# TFT-Display.net
KiCad netlist of a schematic drawn in EAGLE
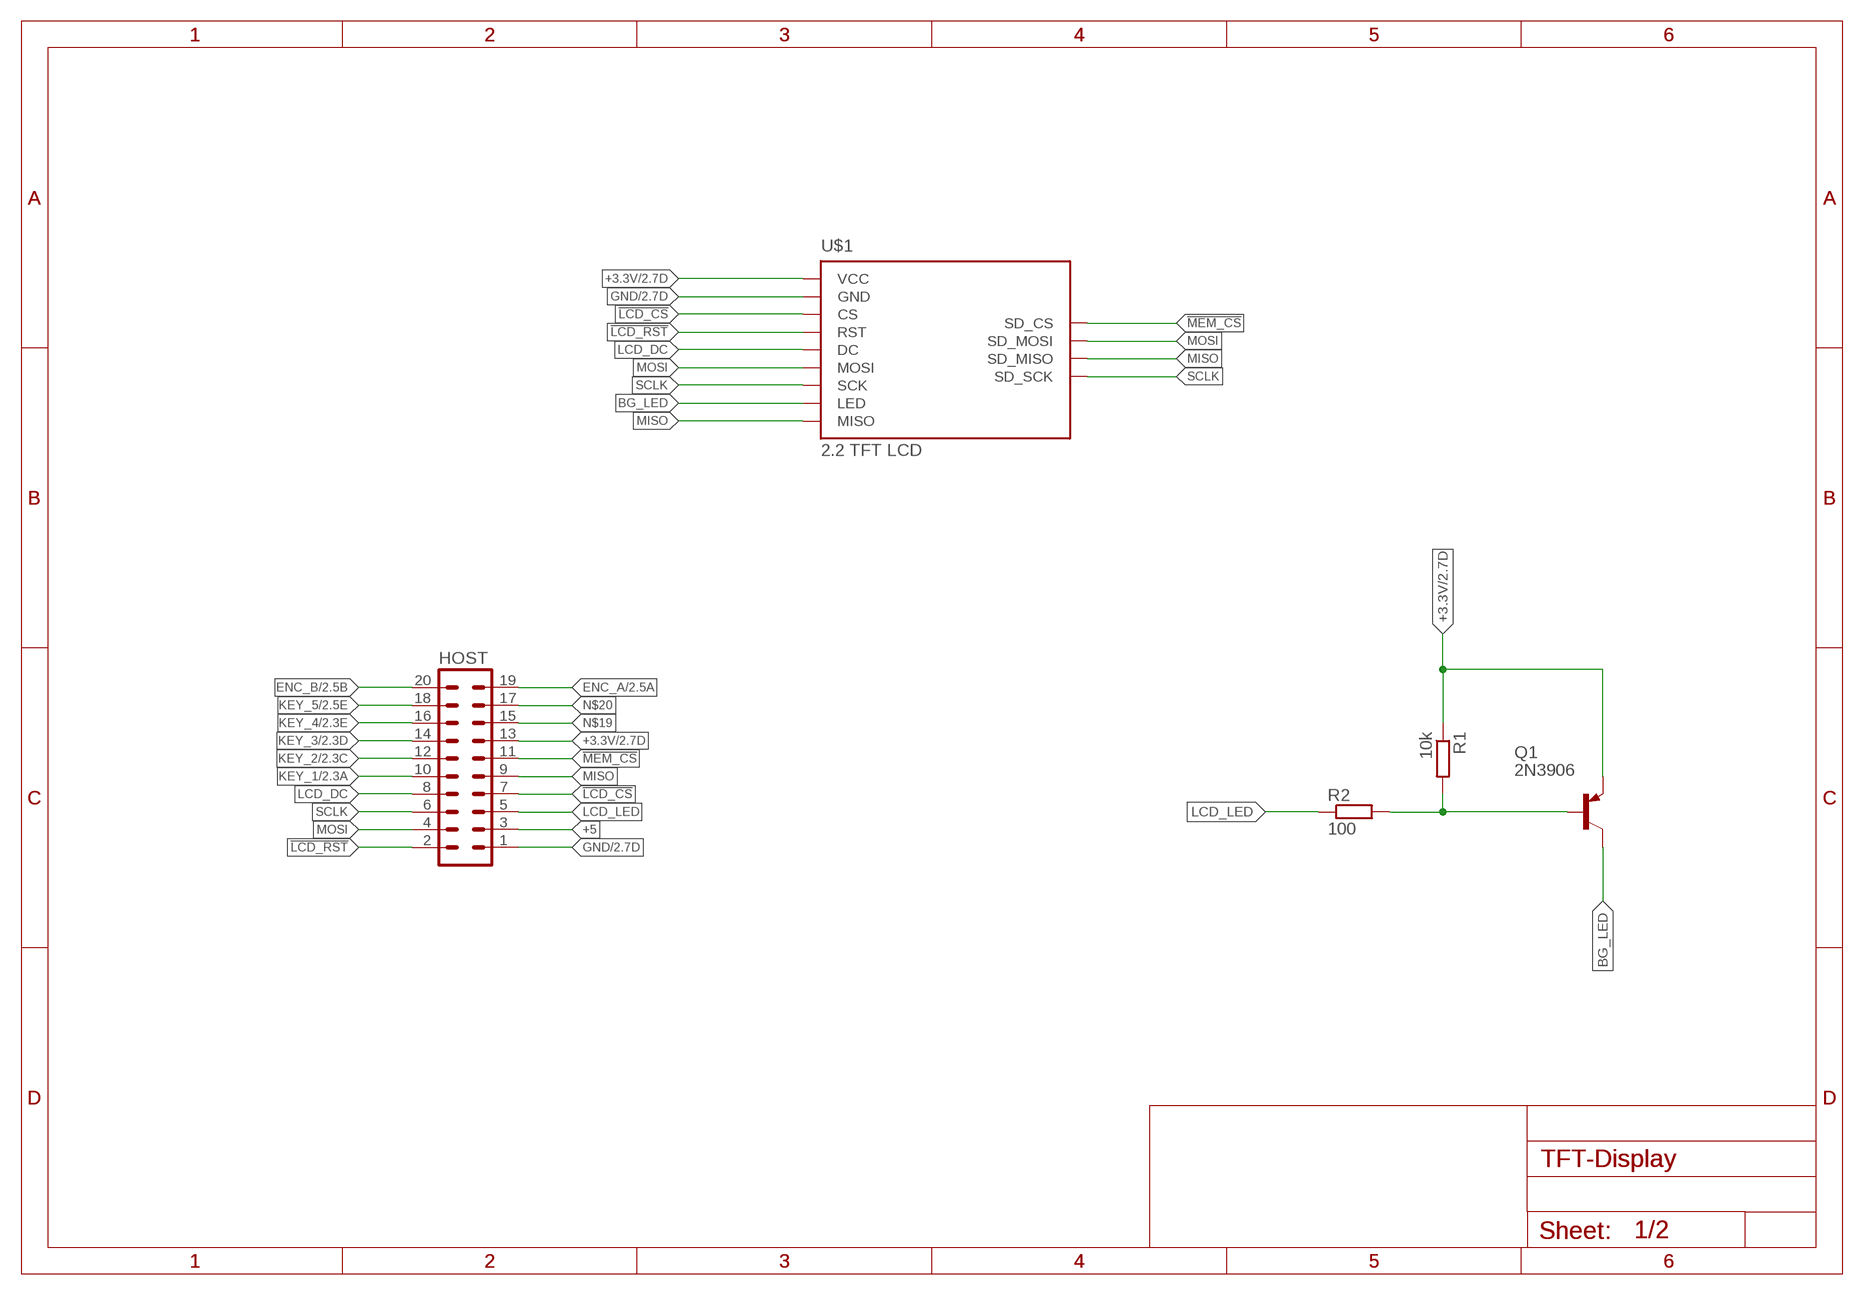
[diagram p0: schematic, sheet 1]
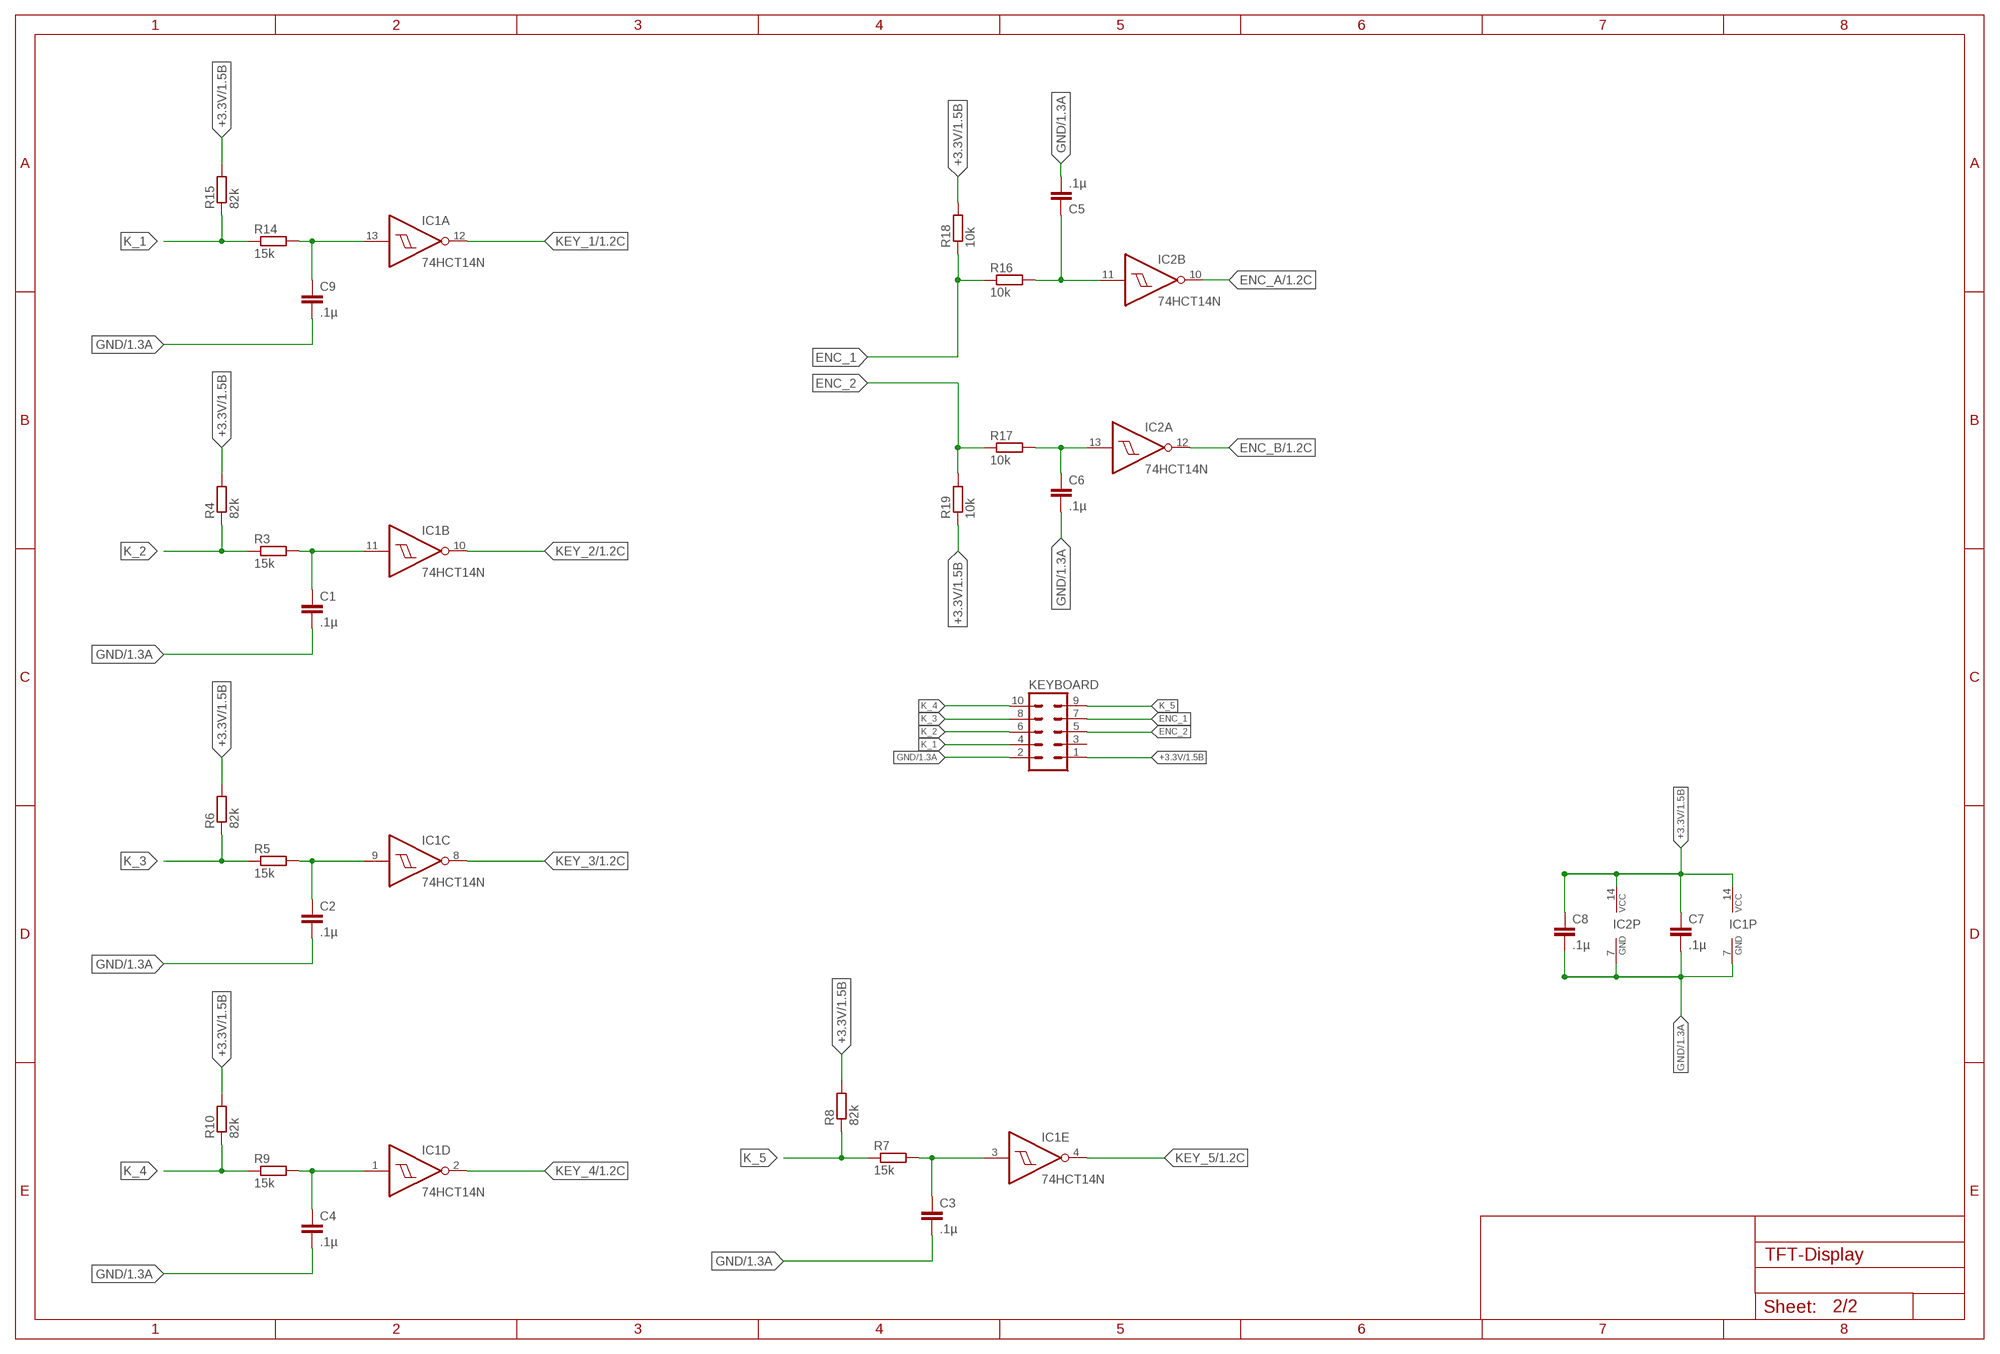
[diagram p1: schematic, sheet 2]

(export (version "E")
  (design (tool "Eeschema 10.0.6"))
  (components
    (comp (ref "C1")
      (value ".1µ")
      (footprint "eagle-import:C025-024X044")
      (libsource (lib "eagle-import") (part "C-EU025-024X044"))
    )
    (comp (ref "C2")
      (value ".1µ")
      (footprint "eagle-import:C025-024X044")
      (libsource (lib "eagle-import") (part "C-EU025-024X044"))
    )
    (comp (ref "C3")
      (value ".1µ")
      (footprint "eagle-import:C025-024X044")
      (libsource (lib "eagle-import") (part "C-EU025-024X044"))
    )
    (comp (ref "C4")
      (value ".1µ")
      (footprint "eagle-import:C025-024X044")
      (libsource (lib "eagle-import") (part "C-EU025-024X044"))
    )
    (comp (ref "C5")
      (value ".1µ")
      (footprint "eagle-import:C025-024X044")
      (libsource (lib "eagle-import") (part "C-EU025-024X044"))
    )
    (comp (ref "C6")
      (value ".1µ")
      (footprint "eagle-import:C025-024X044")
      (libsource (lib "eagle-import") (part "C-EU025-024X044"))
    )
    (comp (ref "C7")
      (value ".1µ")
      (footprint "eagle-import:C025-024X044")
      (libsource (lib "eagle-import") (part "C-EU025-024X044"))
    )
    (comp (ref "C8")
      (value ".1µ")
      (footprint "eagle-import:C025-024X044")
      (libsource (lib "eagle-import") (part "C-EU025-024X044"))
    )
    (comp (ref "C9")
      (value ".1µ")
      (footprint "eagle-import:C025-024X044")
      (libsource (lib "eagle-import") (part "C-EU025-024X044"))
    )
    (comp (ref "IC1")
      (value "74HCT14N")
      (footprint "eagle-import:DIL14")
      (libsource (lib "eagle-import") (part "7414NHCT"))
    )
    (comp (ref "IC2")
      (value "74HCT14N")
      (footprint "eagle-import:DIL14")
      (libsource (lib "eagle-import") (part "7414NHCT"))
    )
    (comp (ref "KEYBOARD")
      (value "ML10L")
      (footprint "eagle-import:ML10L")
      (libsource (lib "eagle-import") (part "ML10L"))
    )
    (comp (ref "R3")
      (value "15k")
      (footprint "eagle-import:0204_7")
      (libsource (lib "eagle-import") (part "R-EU_0204/7"))
    )
    (comp (ref "R4")
      (value "82k")
      (footprint "eagle-import:0204_7")
      (libsource (lib "eagle-import") (part "R-EU_0204/7"))
    )
    (comp (ref "R5")
      (value "15k")
      (footprint "eagle-import:0204_7")
      (libsource (lib "eagle-import") (part "R-EU_0204/7"))
    )
    (comp (ref "R6")
      (value "82k")
      (footprint "eagle-import:0204_7")
      (libsource (lib "eagle-import") (part "R-EU_0204/7"))
    )
    (comp (ref "R7")
      (value "15k")
      (footprint "eagle-import:0204_7")
      (libsource (lib "eagle-import") (part "R-EU_0204/7"))
    )
    (comp (ref "R8")
      (value "82k")
      (footprint "eagle-import:0204_7")
      (libsource (lib "eagle-import") (part "R-EU_0204/7"))
    )
    (comp (ref "R9")
      (value "15k")
      (footprint "eagle-import:0204_7")
      (libsource (lib "eagle-import") (part "R-EU_0204/7"))
    )
    (comp (ref "R10")
      (value "82k")
      (footprint "eagle-import:0204_7")
      (libsource (lib "eagle-import") (part "R-EU_0204/7"))
    )
    (comp (ref "R14")
      (value "15k")
      (footprint "eagle-import:0204_7")
      (libsource (lib "eagle-import") (part "R-EU_0204/7"))
    )
    (comp (ref "R15")
      (value "82k")
      (footprint "eagle-import:0204_7")
      (libsource (lib "eagle-import") (part "R-EU_0204/7"))
    )
    (comp (ref "R16")
      (value "10k")
      (footprint "eagle-import:0204_7")
      (libsource (lib "eagle-import") (part "R-EU_0204/7"))
    )
    (comp (ref "R17")
      (value "10k")
      (footprint "eagle-import:0204_7")
      (libsource (lib "eagle-import") (part "R-EU_0204/7"))
    )
    (comp (ref "R18")
      (value "10k")
      (footprint "eagle-import:0204_7")
      (libsource (lib "eagle-import") (part "R-EU_0204/7"))
    )
    (comp (ref "R19")
      (value "10k")
      (footprint "eagle-import:0204_7")
      (libsource (lib "eagle-import") (part "R-EU_0204/7"))
    )
    (comp (ref "HOST")
      (value "ML20L")
      (footprint "eagle-import:ML20L")
      (libsource (lib "eagle-import") (part "ML20L"))
    )
    (comp (ref "Q1")
      (value "2N3906")
      (footprint "eagle-import:TO92")
      (libsource (lib "eagle-import") (part "2N3906"))
    )
    (comp (ref "R1")
      (value "10k")
      (footprint "eagle-import:0204_7")
      (libsource (lib "eagle-import") (part "R-EU_0204/7"))
    )
    (comp (ref "R2")
      (value "100")
      (footprint "eagle-import:0204_7")
      (libsource (lib "eagle-import") (part "R-EU_0204/7"))
    )
    (comp (ref "U$1")
      (value "2.2_TFT_LCDNEW")
      (footprint "eagle-import:2.2_TFT_LCD_LEDSEE")
      (libsource (lib "eagle-import") (part "2.2_TFT_LCDNEW"))
    )
  )
  (nets
    (net (code "1") (name "+3.3V") (class "Default")
      (node (ref "C7") (pin "1") (pinfunction "1_1") (pintype "passive"))
      (node (ref "C8") (pin "1") (pinfunction "1_1") (pintype "passive"))
      (node (ref "HOST") (pin "13") (pinfunction "13_13") (pintype "passive"))
      (node (ref "IC1") (pin "14") (pinfunction "VCC_14") (pintype "power_in"))
      (node (ref "IC2") (pin "14") (pinfunction "VCC_14") (pintype "power_in"))
      (node (ref "KEYBOARD") (pin "1") (pinfunction "1_1") (pintype "passive"))
      (node (ref "Q1") (pin "3") (pinfunction "E_3") (pintype "passive"))
      (node (ref "R1") (pin "1") (pinfunction "1_1") (pintype "passive"))
      (node (ref "R10") (pin "2") (pinfunction "2_2") (pintype "passive"))
      (node (ref "R15") (pin "2") (pinfunction "2_2") (pintype "passive"))
      (node (ref "R18") (pin "2") (pinfunction "2_2") (pintype "passive"))
      (node (ref "R19") (pin "1") (pinfunction "1_1") (pintype "passive"))
      (node (ref "R4") (pin "2") (pinfunction "2_2") (pintype "passive"))
      (node (ref "R6") (pin "2") (pinfunction "2_2") (pintype "passive"))
      (node (ref "R8") (pin "2") (pinfunction "2_2") (pintype "passive"))
      (node (ref "U$1") (pin "P$5_VCC") (pinfunction "VCC_P$5_VCC") (pintype "power_in"))
    )
    (net (code "2") (name "+5") (class "Default")
      (node (ref "HOST") (pin "3") (pinfunction "3_3") (pintype "passive"))
    )
    (net (code "3") (name "BG_LED") (class "Default")
      (node (ref "Q1") (pin "1") (pinfunction "C_1") (pintype "passive"))
      (node (ref "U$1") (pin "P$8_LED") (pinfunction "LED_P$8_LED") (pintype "bidirectional"))
    )
    (net (code "4") (name "ENC_1") (class "Default")
      (node (ref "KEYBOARD") (pin "7") (pinfunction "7_7") (pintype "passive"))
      (node (ref "R16") (pin "1") (pinfunction "1_1") (pintype "passive"))
      (node (ref "R18") (pin "1") (pinfunction "1_1") (pintype "passive"))
    )
    (net (code "5") (name "ENC_2") (class "Default")
      (node (ref "KEYBOARD") (pin "5") (pinfunction "5_5") (pintype "passive"))
      (node (ref "R17") (pin "1") (pinfunction "1_1") (pintype "passive"))
      (node (ref "R19") (pin "2") (pinfunction "2_2") (pintype "passive"))
    )
    (net (code "6") (name "ENC_A") (class "Default")
      (node (ref "HOST") (pin "19") (pinfunction "19_19") (pintype "passive"))
      (node (ref "IC2") (pin "10") (pinfunction "O_10") (pintype "output"))
    )
    (net (code "7") (name "ENC_B") (class "Default")
      (node (ref "HOST") (pin "20") (pinfunction "20_20") (pintype "passive"))
      (node (ref "IC2") (pin "12") (pinfunction "O_12") (pintype "output"))
    )
    (net (code "8") (name "GND") (class "Default")
      (node (ref "C1") (pin "2") (pinfunction "2_2") (pintype "passive"))
      (node (ref "C2") (pin "2") (pinfunction "2_2") (pintype "passive"))
      (node (ref "C3") (pin "2") (pinfunction "2_2") (pintype "passive"))
      (node (ref "C4") (pin "2") (pinfunction "2_2") (pintype "passive"))
      (node (ref "C5") (pin "2") (pinfunction "2_2") (pintype "passive"))
      (node (ref "C6") (pin "2") (pinfunction "2_2") (pintype "passive"))
      (node (ref "C7") (pin "2") (pinfunction "2_2") (pintype "passive"))
      (node (ref "C8") (pin "2") (pinfunction "2_2") (pintype "passive"))
      (node (ref "C9") (pin "2") (pinfunction "2_2") (pintype "passive"))
      (node (ref "HOST") (pin "1") (pinfunction "1_1") (pintype "passive"))
      (node (ref "IC1") (pin "7") (pinfunction "GND_7") (pintype "power_in"))
      (node (ref "IC2") (pin "7") (pinfunction "GND_7") (pintype "power_in"))
      (node (ref "KEYBOARD") (pin "2") (pinfunction "2_2") (pintype "passive"))
      (node (ref "U$1") (pin "P$4_GND") (pinfunction "GND_P$4_GND") (pintype "power_in"))
    )
    (net (code "9") (name "KEY_1") (class "Default")
      (node (ref "HOST") (pin "10") (pinfunction "10_10") (pintype "passive"))
      (node (ref "IC1") (pin "12") (pinfunction "O_12") (pintype "output"))
    )
    (net (code "10") (name "KEY_2") (class "Default")
      (node (ref "HOST") (pin "12") (pinfunction "12_12") (pintype "passive"))
      (node (ref "IC1") (pin "10") (pinfunction "O_10") (pintype "output"))
    )
    (net (code "11") (name "KEY_3") (class "Default")
      (node (ref "HOST") (pin "14") (pinfunction "14_14") (pintype "passive"))
      (node (ref "IC1") (pin "8") (pinfunction "O_8") (pintype "output"))
    )
    (net (code "12") (name "KEY_4") (class "Default")
      (node (ref "HOST") (pin "16") (pinfunction "16_16") (pintype "passive"))
      (node (ref "IC1") (pin "2") (pinfunction "O_2") (pintype "output"))
    )
    (net (code "13") (name "KEY_5") (class "Default")
      (node (ref "HOST") (pin "18") (pinfunction "18_18") (pintype "passive"))
      (node (ref "IC1") (pin "4") (pinfunction "O_4") (pintype "output"))
    )
    (net (code "14") (name "K_1") (class "Default")
      (node (ref "KEYBOARD") (pin "4") (pinfunction "4_4") (pintype "passive"))
      (node (ref "R14") (pin "1") (pinfunction "1_1") (pintype "passive"))
      (node (ref "R15") (pin "1") (pinfunction "1_1") (pintype "passive"))
    )
    (net (code "15") (name "K_2") (class "Default")
      (node (ref "KEYBOARD") (pin "6") (pinfunction "6_6") (pintype "passive"))
      (node (ref "R3") (pin "1") (pinfunction "1_1") (pintype "passive"))
      (node (ref "R4") (pin "1") (pinfunction "1_1") (pintype "passive"))
    )
    (net (code "16") (name "K_3") (class "Default")
      (node (ref "KEYBOARD") (pin "8") (pinfunction "8_8") (pintype "passive"))
      (node (ref "R5") (pin "1") (pinfunction "1_1") (pintype "passive"))
      (node (ref "R6") (pin "1") (pinfunction "1_1") (pintype "passive"))
    )
    (net (code "17") (name "K_4") (class "Default")
      (node (ref "KEYBOARD") (pin "10") (pinfunction "10_10") (pintype "passive"))
      (node (ref "R10") (pin "1") (pinfunction "1_1") (pintype "passive"))
      (node (ref "R9") (pin "1") (pinfunction "1_1") (pintype "passive"))
    )
    (net (code "18") (name "K_5") (class "Default")
      (node (ref "KEYBOARD") (pin "9") (pinfunction "9_9") (pintype "passive"))
      (node (ref "R7") (pin "1") (pinfunction "1_1") (pintype "passive"))
      (node (ref "R8") (pin "1") (pinfunction "1_1") (pintype "passive"))
    )
    (net (code "19") (name "LCD_DC") (class "Default")
      (node (ref "HOST") (pin "8") (pinfunction "8_8") (pintype "passive"))
      (node (ref "U$1") (pin "P$1_DC") (pinfunction "DC_P$1_DC") (pintype "bidirectional"))
    )
    (net (code "20") (name "LCD_LED") (class "Default")
      (node (ref "HOST") (pin "5") (pinfunction "5_5") (pintype "passive"))
      (node (ref "R2") (pin "1") (pinfunction "1_1") (pintype "passive"))
    )
    (net (code "21") (name "MISO") (class "Default")
      (node (ref "HOST") (pin "9") (pinfunction "9_9") (pintype "passive"))
      (node (ref "U$1") (pin "P$3_SD_MISO") (pinfunction "SD_MISO_P$3_SD_MISO") (pintype "bidirectional"))
      (node (ref "U$1") (pin "P$9_MISO") (pinfunction "MISO_P$9_MISO") (pintype "bidirectional"))
    )
    (net (code "22") (name "MOSI") (class "Default")
      (node (ref "HOST") (pin "4") (pinfunction "4_4") (pintype "passive"))
      (node (ref "U$1") (pin "P$1_SD_MOSI") (pinfunction "SD_MOSI_P$1_SD_MOSI") (pintype "bidirectional"))
      (node (ref "U$1") (pin "P$6_MOSI") (pinfunction "MOSI_P$6_MOSI") (pintype "bidirectional"))
    )
    (net (code "23") (name "N$19") (class "Default")
      (node (ref "HOST") (pin "15") (pinfunction "15_15") (pintype "passive"))
    )
    (net (code "24") (name "N$20") (class "Default")
      (node (ref "HOST") (pin "17") (pinfunction "17_17") (pintype "passive"))
    )
    (net (code "25") (name "Net-(IC1A-I)") (class "Default")
      (node (ref "C9") (pin "1") (pinfunction "1_1") (pintype "passive"))
      (node (ref "IC1") (pin "13") (pinfunction "I_13") (pintype "input"))
      (node (ref "R14") (pin "2") (pinfunction "2_2") (pintype "passive"))
    )
    (net (code "26") (name "Net-(IC1B-I)") (class "Default")
      (node (ref "C1") (pin "1") (pinfunction "1_1") (pintype "passive"))
      (node (ref "IC1") (pin "11") (pinfunction "I_11") (pintype "input"))
      (node (ref "R3") (pin "2") (pinfunction "2_2") (pintype "passive"))
    )
    (net (code "27") (name "Net-(IC1C-I)") (class "Default")
      (node (ref "C2") (pin "1") (pinfunction "1_1") (pintype "passive"))
      (node (ref "IC1") (pin "9") (pinfunction "I_9") (pintype "input"))
      (node (ref "R5") (pin "2") (pinfunction "2_2") (pintype "passive"))
    )
    (net (code "28") (name "Net-(IC1D-I)") (class "Default")
      (node (ref "C4") (pin "1") (pinfunction "1_1") (pintype "passive"))
      (node (ref "IC1") (pin "1") (pinfunction "I_1") (pintype "input"))
      (node (ref "R9") (pin "2") (pinfunction "2_2") (pintype "passive"))
    )
    (net (code "29") (name "Net-(IC1E-I)") (class "Default")
      (node (ref "C3") (pin "1") (pinfunction "1_1") (pintype "passive"))
      (node (ref "IC1") (pin "3") (pinfunction "I_3") (pintype "input"))
      (node (ref "R7") (pin "2") (pinfunction "2_2") (pintype "passive"))
    )
    (net (code "30") (name "Net-(IC2A-I)") (class "Default")
      (node (ref "C6") (pin "1") (pinfunction "1_1") (pintype "passive"))
      (node (ref "IC2") (pin "13") (pinfunction "I_13") (pintype "input"))
      (node (ref "R17") (pin "2") (pinfunction "2_2") (pintype "passive"))
    )
    (net (code "31") (name "Net-(IC2B-I)") (class "Default")
      (node (ref "C5") (pin "1") (pinfunction "1_1") (pintype "passive"))
      (node (ref "IC2") (pin "11") (pinfunction "I_11") (pintype "input"))
      (node (ref "R16") (pin "2") (pinfunction "2_2") (pintype "passive"))
    )
    (net (code "32") (name "Net-(Q1-B)") (class "Default")
      (node (ref "Q1") (pin "2") (pinfunction "B_2") (pintype "passive"))
      (node (ref "R1") (pin "2") (pinfunction "2_2") (pintype "passive"))
      (node (ref "R2") (pin "2") (pinfunction "2_2") (pintype "passive"))
    )
    (net (code "33") (name "SCLK") (class "Default")
      (node (ref "HOST") (pin "6") (pinfunction "6_6") (pintype "passive"))
      (node (ref "U$1") (pin "P$4_SD_SCK") (pinfunction "SD_SCK_P$4_SD_SCK") (pintype "bidirectional"))
      (node (ref "U$1") (pin "P$7_SCK") (pinfunction "SCK_P$7_SCK") (pintype "bidirectional"))
    )
    (net (code "34") (name "unconnected-(KEYBOARD-Pad3)") (class "Default")
      (node (ref "KEYBOARD") (pin "3") (pinfunction "3_3") (pintype "passive"))
    )
    (net (code "35") (name "~{LCD_CS}") (class "Default")
      (node (ref "HOST") (pin "7") (pinfunction "7_7") (pintype "passive"))
      (node (ref "U$1") (pin "P$3_CS") (pinfunction "CS_P$3_CS") (pintype "bidirectional"))
    )
    (net (code "36") (name "~{LCD_RST}") (class "Default")
      (node (ref "HOST") (pin "2") (pinfunction "2_2") (pintype "passive"))
      (node (ref "U$1") (pin "P$2_RESET") (pinfunction "RST_P$2_RESET") (pintype "bidirectional"))
    )
    (net (code "37") (name "~{MEM_CS}") (class "Default")
      (node (ref "HOST") (pin "11") (pinfunction "11_11") (pintype "passive"))
      (node (ref "U$1") (pin "P$2_SD_CS") (pinfunction "SD_CS_P$2_SD_CS") (pintype "bidirectional"))
    )
  )
)
